# Cameralink_Karmann.net
KiCad netlist of a schematic drawn in EAGLE
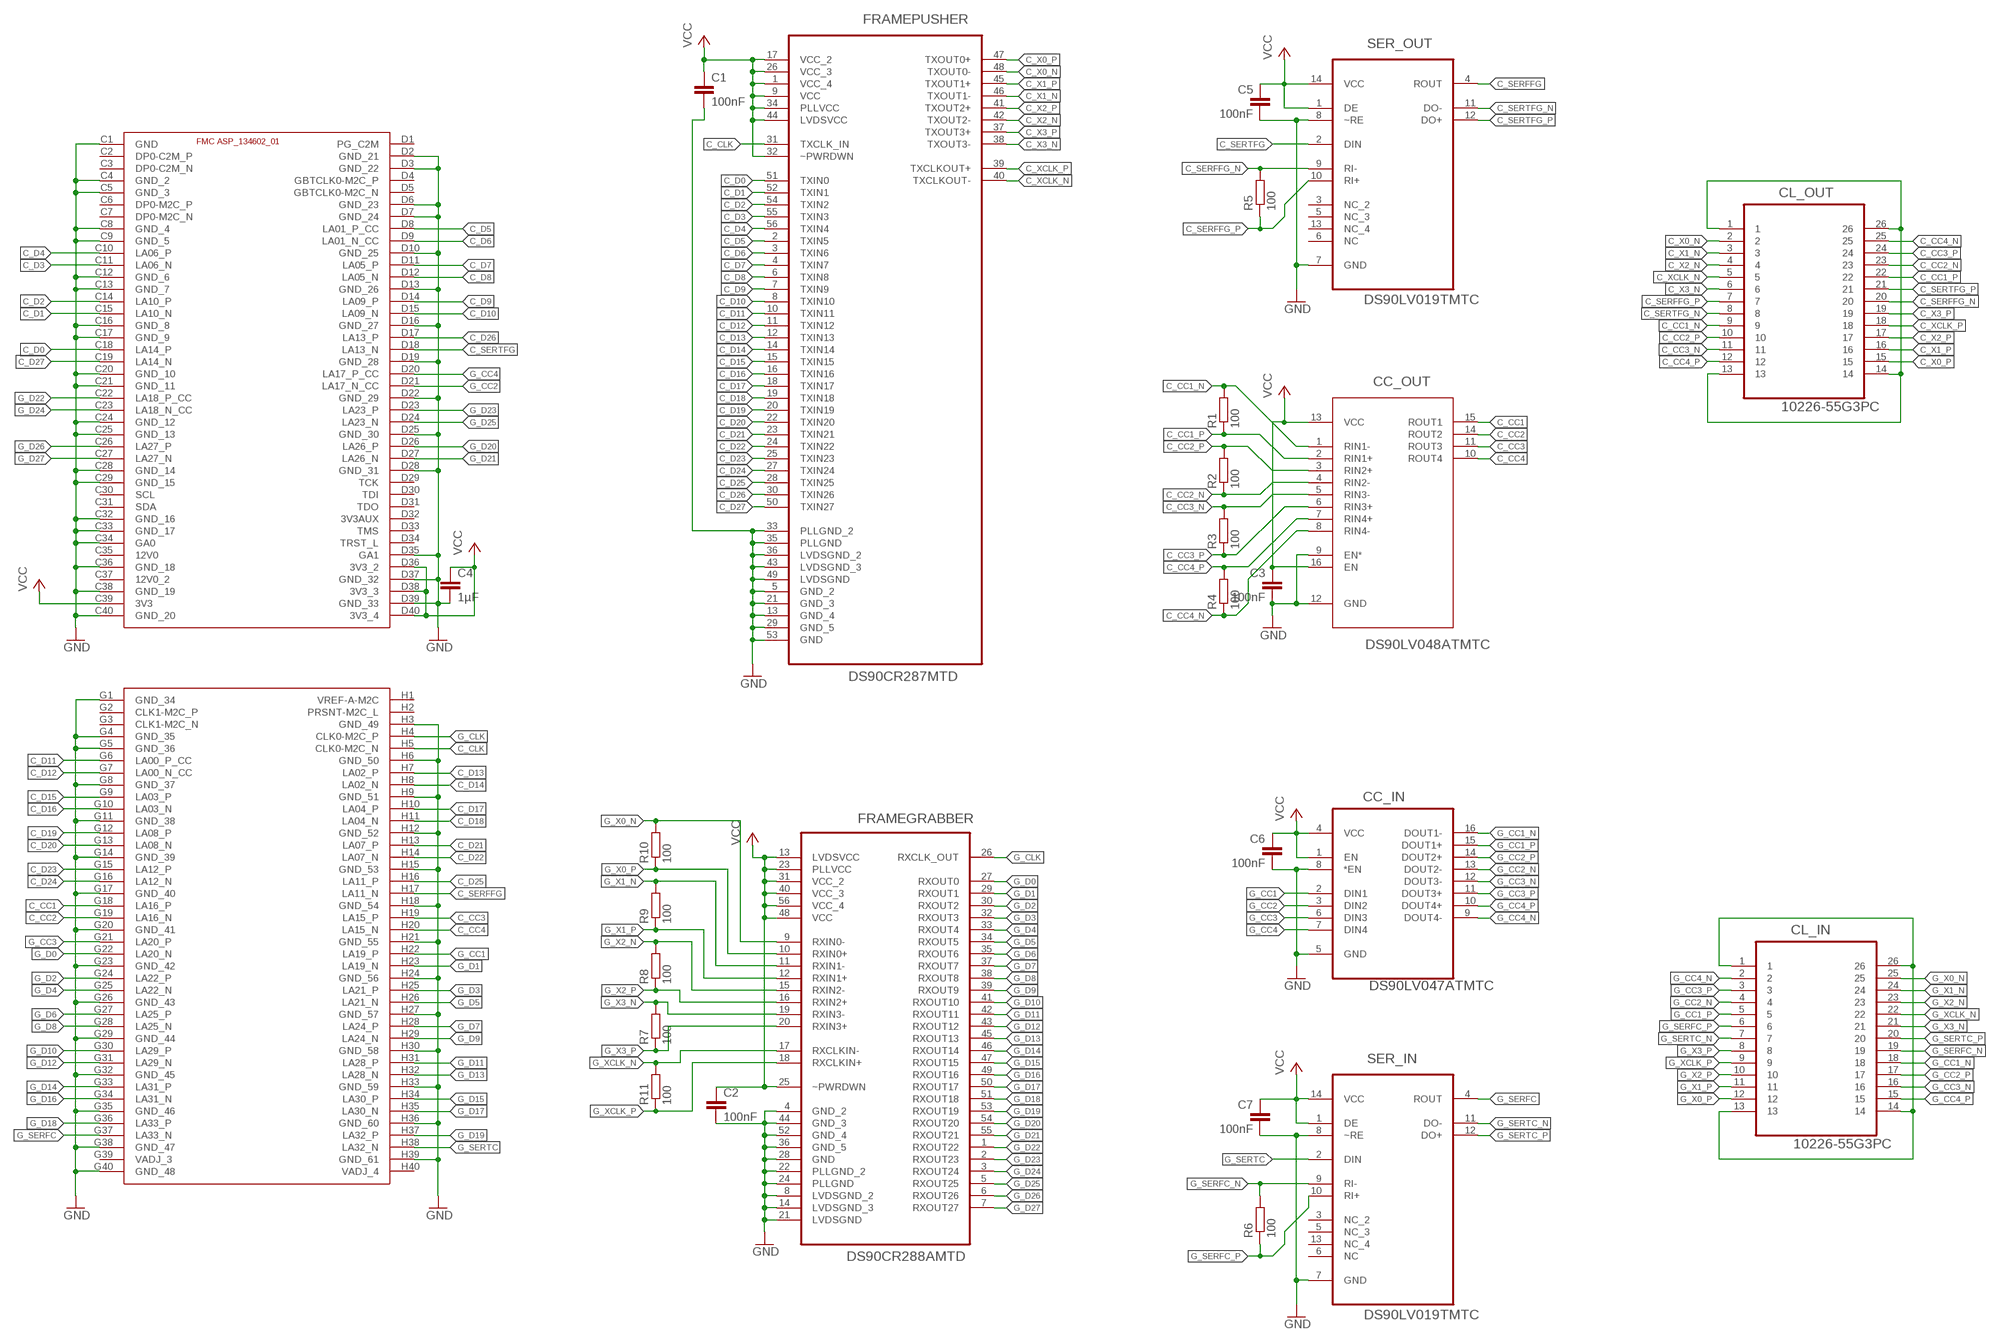
[diagram p0: schematic, sheet 1]

(export (version "E")
  (design (tool "Eeschema 10.0.6"))
  (components
    (comp (ref "C1")
      (value "100nF")
      (footprint "eagle-import:C1206")
      (libsource (lib "eagle-import") (part "C-EUC1206"))
    )
    (comp (ref "C2")
      (value "100nF")
      (footprint "eagle-import:C1206")
      (libsource (lib "eagle-import") (part "C-EUC1206"))
    )
    (comp (ref "C3")
      (value "100nF")
      (footprint "eagle-import:C1206")
      (libsource (lib "eagle-import") (part "C-EUC1206"))
    )
    (comp (ref "C4")
      (value "1µF")
      (footprint "eagle-import:C1206")
      (libsource (lib "eagle-import") (part "C-EUC1206"))
    )
    (comp (ref "C5")
      (value "100nF")
      (footprint "eagle-import:C1206")
      (libsource (lib "eagle-import") (part "C-EUC1206"))
    )
    (comp (ref "C6")
      (value "100nF")
      (footprint "eagle-import:C1206")
      (libsource (lib "eagle-import") (part "C-EUC1206"))
    )
    (comp (ref "C7")
      (value "100nF")
      (footprint "eagle-import:C1206")
      (libsource (lib "eagle-import") (part "C-EUC1206"))
    )
    (comp (ref "CC_IN")
      (value "DS90LV047ATMTC")
      (footprint "eagle-import:SOP65P640X110-16N")
      (libsource (lib "eagle-import") (part "DS90LV047ATMTC"))
    )
    (comp (ref "CC_OUT")
      (value "DS90LV048ATMTC")
      (footprint "eagle-import:SOP65P640X110-16N")
      (libsource (lib "eagle-import") (part "DS90LV048ATMTC"))
    )
    (comp (ref "CL_IN")
      (value "10226-55G3PC")
      (footprint "eagle-import:3M_10226-55G3PC")
      (libsource (lib "eagle-import") (part "10226-55G3PC"))
    )
    (comp (ref "CL_OUT")
      (value "10226-55G3PC")
      (footprint "eagle-import:3M_10226-55G3PC")
      (libsource (lib "eagle-import") (part "10226-55G3PC"))
    )
    (comp (ref "FRAMEGRABBER")
      (value "DS90CR288AMTD")
      (footprint "eagle-import:SOP50P810X110-56N")
      (libsource (lib "eagle-import") (part "DS90CR288AMTD"))
    )
    (comp (ref "FRAMEPUSHER")
      (value "DS90CR287MTD")
      (footprint "eagle-import:SOP50P810X110-56N")
      (libsource (lib "eagle-import") (part "DS90CR287MTD"))
    )
    (comp (ref "R1")
      (value "100")
      (footprint "eagle-import:R1206")
      (libsource (lib "eagle-import") (part "R-EU_R1206"))
    )
    (comp (ref "R2")
      (value "100")
      (footprint "eagle-import:R1206")
      (libsource (lib "eagle-import") (part "R-EU_R1206"))
    )
    (comp (ref "R3")
      (value "100")
      (footprint "eagle-import:R1206")
      (libsource (lib "eagle-import") (part "R-EU_R1206"))
    )
    (comp (ref "R4")
      (value "100")
      (footprint "eagle-import:R1206")
      (libsource (lib "eagle-import") (part "R-EU_R1206"))
    )
    (comp (ref "R5")
      (value "100")
      (footprint "eagle-import:R1206")
      (libsource (lib "eagle-import") (part "R-EU_R1206"))
    )
    (comp (ref "R6")
      (value "100")
      (footprint "eagle-import:R1206")
      (libsource (lib "eagle-import") (part "R-EU_R1206"))
    )
    (comp (ref "R7")
      (value "100")
      (footprint "eagle-import:R1206")
      (libsource (lib "eagle-import") (part "R-EU_R1206"))
    )
    (comp (ref "R8")
      (value "100")
      (footprint "eagle-import:R1206")
      (libsource (lib "eagle-import") (part "R-EU_R1206"))
    )
    (comp (ref "R9")
      (value "100")
      (footprint "eagle-import:R1206")
      (libsource (lib "eagle-import") (part "R-EU_R1206"))
    )
    (comp (ref "R10")
      (value "100")
      (footprint "eagle-import:R1206")
      (libsource (lib "eagle-import") (part "R-EU_R1206"))
    )
    (comp (ref "R11")
      (value "100")
      (footprint "eagle-import:R1206")
      (libsource (lib "eagle-import") (part "R-EU_R1206"))
    )
    (comp (ref "SER_IN")
      (value "DS90LV019TMTC")
      (footprint "eagle-import:SOP65P640X110-14N")
      (libsource (lib "eagle-import") (part "DS90LV019TMTC"))
    )
    (comp (ref "SER_OUT")
      (value "DS90LV019TMTC")
      (footprint "eagle-import:SOP65P640X110-14N")
      (libsource (lib "eagle-import") (part "DS90LV019TMTC"))
    )
    (comp (ref "U$1")
      (value "ASP_134602_01")
      (footprint "eagle-import:ASP_134602_01")
      (libsource (lib "eagle-import") (part "ASP_134602_01"))
    )
  )
  (nets
    (net (code "1") (name "C_CC1") (class "Default")
      (node (ref "CC_OUT") (pin "15") (pinfunction "ROUT1_15") (pintype "output"))
      (node (ref "U$1") (pin "G18") (pinfunction "LA16_P_G18") (pintype "bidirectional"))
    )
    (net (code "2") (name "C_CC1_N") (class "Default")
      (node (ref "CC_OUT") (pin "1") (pinfunction "RIN1-_1") (pintype "input"))
      (node (ref "CL_OUT") (pin "9") (pinfunction "9_9") (pintype "passive"))
      (node (ref "R1") (pin "2") (pinfunction "2_2") (pintype "passive"))
    )
    (net (code "3") (name "C_CC1_P") (class "Default")
      (node (ref "CC_OUT") (pin "2") (pinfunction "RIN1+_2") (pintype "input"))
      (node (ref "CL_OUT") (pin "22") (pinfunction "22_22") (pintype "passive"))
      (node (ref "R1") (pin "1") (pinfunction "1_1") (pintype "passive"))
    )
    (net (code "4") (name "C_CC2") (class "Default")
      (node (ref "CC_OUT") (pin "14") (pinfunction "ROUT2_14") (pintype "output"))
      (node (ref "U$1") (pin "G19") (pinfunction "LA16_N_G19") (pintype "bidirectional"))
    )
    (net (code "5") (name "C_CC2_N") (class "Default")
      (node (ref "CC_OUT") (pin "4") (pinfunction "RIN2-_4") (pintype "input"))
      (node (ref "CL_OUT") (pin "23") (pinfunction "23_23") (pintype "passive"))
      (node (ref "R2") (pin "1") (pinfunction "1_1") (pintype "passive"))
    )
    (net (code "6") (name "C_CC2_P") (class "Default")
      (node (ref "CC_OUT") (pin "3") (pinfunction "RIN2+_3") (pintype "input"))
      (node (ref "CL_OUT") (pin "10") (pinfunction "10_10") (pintype "passive"))
      (node (ref "R2") (pin "2") (pinfunction "2_2") (pintype "passive"))
    )
    (net (code "7") (name "C_CC3") (class "Default")
      (node (ref "CC_OUT") (pin "11") (pinfunction "ROUT3_11") (pintype "output"))
      (node (ref "U$1") (pin "H19") (pinfunction "LA15_P_H19") (pintype "bidirectional"))
    )
    (net (code "8") (name "C_CC3_N") (class "Default")
      (node (ref "CC_OUT") (pin "5") (pinfunction "RIN3-_5") (pintype "input"))
      (node (ref "CL_OUT") (pin "11") (pinfunction "11_11") (pintype "passive"))
      (node (ref "R3") (pin "2") (pinfunction "2_2") (pintype "passive"))
    )
    (net (code "9") (name "C_CC3_P") (class "Default")
      (node (ref "CC_OUT") (pin "6") (pinfunction "RIN3+_6") (pintype "input"))
      (node (ref "CL_OUT") (pin "24") (pinfunction "24_24") (pintype "passive"))
      (node (ref "R3") (pin "1") (pinfunction "1_1") (pintype "passive"))
    )
    (net (code "10") (name "C_CC4") (class "Default")
      (node (ref "CC_OUT") (pin "10") (pinfunction "ROUT4_10") (pintype "output"))
      (node (ref "U$1") (pin "H20") (pinfunction "LA15_N_H20") (pintype "bidirectional"))
    )
    (net (code "11") (name "C_CC4_N") (class "Default")
      (node (ref "CC_OUT") (pin "8") (pinfunction "RIN4-_8") (pintype "input"))
      (node (ref "CL_OUT") (pin "25") (pinfunction "25_25") (pintype "passive"))
      (node (ref "R4") (pin "1") (pinfunction "1_1") (pintype "passive"))
    )
    (net (code "12") (name "C_CC4_P") (class "Default")
      (node (ref "CC_OUT") (pin "7") (pinfunction "RIN4+_7") (pintype "input"))
      (node (ref "CL_OUT") (pin "12") (pinfunction "12_12") (pintype "passive"))
      (node (ref "R4") (pin "2") (pinfunction "2_2") (pintype "passive"))
    )
    (net (code "13") (name "C_CLK") (class "Default")
      (node (ref "FRAMEPUSHER") (pin "31") (pinfunction "TXCLK_IN_31") (pintype "input"))
      (node (ref "U$1") (pin "H5") (pinfunction "CLK0-M2C_N_H5") (pintype "bidirectional"))
    )
    (net (code "14") (name "C_D0") (class "Default")
      (node (ref "FRAMEPUSHER") (pin "51") (pinfunction "TXIN0_51") (pintype "input"))
      (node (ref "U$1") (pin "C18") (pinfunction "LA14_P_C18") (pintype "bidirectional"))
    )
    (net (code "15") (name "C_D1") (class "Default")
      (node (ref "FRAMEPUSHER") (pin "52") (pinfunction "TXIN1_52") (pintype "input"))
      (node (ref "U$1") (pin "C15") (pinfunction "LA10_N_C15") (pintype "bidirectional"))
    )
    (net (code "16") (name "C_D2") (class "Default")
      (node (ref "FRAMEPUSHER") (pin "54") (pinfunction "TXIN2_54") (pintype "input"))
      (node (ref "U$1") (pin "C14") (pinfunction "LA10_P_C14") (pintype "bidirectional"))
    )
    (net (code "17") (name "C_D3") (class "Default")
      (node (ref "FRAMEPUSHER") (pin "55") (pinfunction "TXIN3_55") (pintype "input"))
      (node (ref "U$1") (pin "C11") (pinfunction "LA06_N_C11") (pintype "bidirectional"))
    )
    (net (code "18") (name "C_D4") (class "Default")
      (node (ref "FRAMEPUSHER") (pin "56") (pinfunction "TXIN4_56") (pintype "input"))
      (node (ref "U$1") (pin "C10") (pinfunction "LA06_P_C10") (pintype "bidirectional"))
    )
    (net (code "19") (name "C_D5") (class "Default")
      (node (ref "FRAMEPUSHER") (pin "2") (pinfunction "TXIN5_2") (pintype "input"))
      (node (ref "U$1") (pin "D8") (pinfunction "LA01_P_CC_D8") (pintype "bidirectional"))
    )
    (net (code "20") (name "C_D6") (class "Default")
      (node (ref "FRAMEPUSHER") (pin "3") (pinfunction "TXIN6_3") (pintype "input"))
      (node (ref "U$1") (pin "D9") (pinfunction "LA01_N_CC_D9") (pintype "bidirectional"))
    )
    (net (code "21") (name "C_D7") (class "Default")
      (node (ref "FRAMEPUSHER") (pin "4") (pinfunction "TXIN7_4") (pintype "input"))
      (node (ref "U$1") (pin "D11") (pinfunction "LA05_P_D11") (pintype "bidirectional"))
    )
    (net (code "22") (name "C_D8") (class "Default")
      (node (ref "FRAMEPUSHER") (pin "6") (pinfunction "TXIN8_6") (pintype "input"))
      (node (ref "U$1") (pin "D12") (pinfunction "LA05_N_D12") (pintype "bidirectional"))
    )
    (net (code "23") (name "C_D9") (class "Default")
      (node (ref "FRAMEPUSHER") (pin "7") (pinfunction "TXIN9_7") (pintype "input"))
      (node (ref "U$1") (pin "D14") (pinfunction "LA09_P_D14") (pintype "bidirectional"))
    )
    (net (code "24") (name "C_D10") (class "Default")
      (node (ref "FRAMEPUSHER") (pin "8") (pinfunction "TXIN10_8") (pintype "input"))
      (node (ref "U$1") (pin "D15") (pinfunction "LA09_N_D15") (pintype "bidirectional"))
    )
    (net (code "25") (name "C_D11") (class "Default")
      (node (ref "FRAMEPUSHER") (pin "10") (pinfunction "TXIN11_10") (pintype "input"))
      (node (ref "U$1") (pin "G6") (pinfunction "LA00_P_CC_G6") (pintype "bidirectional"))
    )
    (net (code "26") (name "C_D12") (class "Default")
      (node (ref "FRAMEPUSHER") (pin "11") (pinfunction "TXIN12_11") (pintype "input"))
      (node (ref "U$1") (pin "G7") (pinfunction "LA00_N_CC_G7") (pintype "bidirectional"))
    )
    (net (code "27") (name "C_D13") (class "Default")
      (node (ref "FRAMEPUSHER") (pin "12") (pinfunction "TXIN13_12") (pintype "input"))
      (node (ref "U$1") (pin "H7") (pinfunction "LA02_P_H7") (pintype "bidirectional"))
    )
    (net (code "28") (name "C_D14") (class "Default")
      (node (ref "FRAMEPUSHER") (pin "14") (pinfunction "TXIN14_14") (pintype "input"))
      (node (ref "U$1") (pin "H8") (pinfunction "LA02_N_H8") (pintype "bidirectional"))
    )
    (net (code "29") (name "C_D15") (class "Default")
      (node (ref "FRAMEPUSHER") (pin "15") (pinfunction "TXIN15_15") (pintype "input"))
      (node (ref "U$1") (pin "G9") (pinfunction "LA03_P_G9") (pintype "bidirectional"))
    )
    (net (code "30") (name "C_D16") (class "Default")
      (node (ref "FRAMEPUSHER") (pin "16") (pinfunction "TXIN16_16") (pintype "input"))
      (node (ref "U$1") (pin "G10") (pinfunction "LA03_N_G10") (pintype "bidirectional"))
    )
    (net (code "31") (name "C_D17") (class "Default")
      (node (ref "FRAMEPUSHER") (pin "18") (pinfunction "TXIN17_18") (pintype "input"))
      (node (ref "U$1") (pin "H10") (pinfunction "LA04_P_H10") (pintype "bidirectional"))
    )
    (net (code "32") (name "C_D18") (class "Default")
      (node (ref "FRAMEPUSHER") (pin "19") (pinfunction "TXIN18_19") (pintype "input"))
      (node (ref "U$1") (pin "H11") (pinfunction "LA04_N_H11") (pintype "bidirectional"))
    )
    (net (code "33") (name "C_D19") (class "Default")
      (node (ref "FRAMEPUSHER") (pin "20") (pinfunction "TXIN19_20") (pintype "input"))
      (node (ref "U$1") (pin "G12") (pinfunction "LA08_P_G12") (pintype "bidirectional"))
    )
    (net (code "34") (name "C_D20") (class "Default")
      (node (ref "FRAMEPUSHER") (pin "22") (pinfunction "TXIN20_22") (pintype "input"))
      (node (ref "U$1") (pin "G13") (pinfunction "LA08_N_G13") (pintype "bidirectional"))
    )
    (net (code "35") (name "C_D21") (class "Default")
      (node (ref "FRAMEPUSHER") (pin "23") (pinfunction "TXIN21_23") (pintype "input"))
      (node (ref "U$1") (pin "H13") (pinfunction "LA07_P_H13") (pintype "bidirectional"))
    )
    (net (code "36") (name "C_D22") (class "Default")
      (node (ref "FRAMEPUSHER") (pin "24") (pinfunction "TXIN22_24") (pintype "input"))
      (node (ref "U$1") (pin "H14") (pinfunction "LA07_N_H14") (pintype "bidirectional"))
    )
    (net (code "37") (name "C_D23") (class "Default")
      (node (ref "FRAMEPUSHER") (pin "25") (pinfunction "TXIN23_25") (pintype "input"))
      (node (ref "U$1") (pin "G15") (pinfunction "LA12_P_G15") (pintype "bidirectional"))
    )
    (net (code "38") (name "C_D24") (class "Default")
      (node (ref "FRAMEPUSHER") (pin "27") (pinfunction "TXIN24_27") (pintype "input"))
      (node (ref "U$1") (pin "G16") (pinfunction "LA12_N_G16") (pintype "bidirectional"))
    )
    (net (code "39") (name "C_D25") (class "Default")
      (node (ref "FRAMEPUSHER") (pin "28") (pinfunction "TXIN25_28") (pintype "input"))
      (node (ref "U$1") (pin "H16") (pinfunction "LA11_P_H16") (pintype "bidirectional"))
    )
    (net (code "40") (name "C_D26") (class "Default")
      (node (ref "FRAMEPUSHER") (pin "30") (pinfunction "TXIN26_30") (pintype "input"))
      (node (ref "U$1") (pin "D17") (pinfunction "LA13_P_D17") (pintype "bidirectional"))
    )
    (net (code "41") (name "C_D27") (class "Default")
      (node (ref "FRAMEPUSHER") (pin "50") (pinfunction "TXIN27_50") (pintype "input"))
      (node (ref "U$1") (pin "C19") (pinfunction "LA14_N_C19") (pintype "bidirectional"))
    )
    (net (code "42") (name "C_SERFFG") (class "Default")
      (node (ref "SER_OUT") (pin "4") (pinfunction "ROUT_4") (pintype "output"))
      (node (ref "U$1") (pin "H17") (pinfunction "LA11_N_H17") (pintype "bidirectional"))
    )
    (net (code "43") (name "C_SERFFG_N") (class "Default")
      (node (ref "CL_OUT") (pin "20") (pinfunction "20_20") (pintype "passive"))
      (node (ref "R5") (pin "2") (pinfunction "2_2") (pintype "passive"))
      (node (ref "SER_OUT") (pin "9") (pinfunction "RI-_9") (pintype "input"))
    )
    (net (code "44") (name "C_SERFFG_P") (class "Default")
      (node (ref "CL_OUT") (pin "7") (pinfunction "7_7") (pintype "passive"))
      (node (ref "R5") (pin "1") (pinfunction "1_1") (pintype "passive"))
      (node (ref "SER_OUT") (pin "10") (pinfunction "RI+_10") (pintype "input"))
    )
    (net (code "45") (name "C_SERTFG") (class "Default")
      (node (ref "SER_OUT") (pin "2") (pinfunction "DIN_2") (pintype "input"))
      (node (ref "U$1") (pin "D18") (pinfunction "LA13_N_D18") (pintype "bidirectional"))
    )
    (net (code "46") (name "C_SERTFG_N") (class "Default")
      (node (ref "CL_OUT") (pin "8") (pinfunction "8_8") (pintype "passive"))
      (node (ref "SER_OUT") (pin "11") (pinfunction "DO-_11") (pintype "output"))
    )
    (net (code "47") (name "C_SERTFG_P") (class "Default")
      (node (ref "CL_OUT") (pin "21") (pinfunction "21_21") (pintype "passive"))
      (node (ref "SER_OUT") (pin "12") (pinfunction "DO+_12") (pintype "output"))
    )
    (net (code "48") (name "C_X0_N") (class "Default")
      (node (ref "CL_OUT") (pin "2") (pinfunction "2_2") (pintype "passive"))
      (node (ref "FRAMEPUSHER") (pin "48") (pinfunction "TXOUT0-_48") (pintype "output"))
    )
    (net (code "49") (name "C_X0_P") (class "Default")
      (node (ref "CL_OUT") (pin "15") (pinfunction "15_15") (pintype "passive"))
      (node (ref "FRAMEPUSHER") (pin "47") (pinfunction "TXOUT0+_47") (pintype "output"))
    )
    (net (code "50") (name "C_X1_N") (class "Default")
      (node (ref "CL_OUT") (pin "3") (pinfunction "3_3") (pintype "passive"))
      (node (ref "FRAMEPUSHER") (pin "46") (pinfunction "TXOUT1-_46") (pintype "output"))
    )
    (net (code "51") (name "C_X1_P") (class "Default")
      (node (ref "CL_OUT") (pin "16") (pinfunction "16_16") (pintype "passive"))
      (node (ref "FRAMEPUSHER") (pin "45") (pinfunction "TXOUT1+_45") (pintype "output"))
    )
    (net (code "52") (name "C_X2_N") (class "Default")
      (node (ref "CL_OUT") (pin "4") (pinfunction "4_4") (pintype "passive"))
      (node (ref "FRAMEPUSHER") (pin "42") (pinfunction "TXOUT2-_42") (pintype "output"))
    )
    (net (code "53") (name "C_X2_P") (class "Default")
      (node (ref "CL_OUT") (pin "17") (pinfunction "17_17") (pintype "passive"))
      (node (ref "FRAMEPUSHER") (pin "41") (pinfunction "TXOUT2+_41") (pintype "output"))
    )
    (net (code "54") (name "C_X3_N") (class "Default")
      (node (ref "CL_OUT") (pin "6") (pinfunction "6_6") (pintype "passive"))
      (node (ref "FRAMEPUSHER") (pin "38") (pinfunction "TXOUT3-_38") (pintype "output"))
    )
    (net (code "55") (name "C_X3_P") (class "Default")
      (node (ref "CL_OUT") (pin "19") (pinfunction "19_19") (pintype "passive"))
      (node (ref "FRAMEPUSHER") (pin "37") (pinfunction "TXOUT3+_37") (pintype "output"))
    )
    (net (code "56") (name "C_XCLK_N") (class "Default")
      (node (ref "CL_OUT") (pin "5") (pinfunction "5_5") (pintype "passive"))
      (node (ref "FRAMEPUSHER") (pin "40") (pinfunction "TXCLKOUT-_40") (pintype "output"))
    )
    (net (code "57") (name "C_XCLK_P") (class "Default")
      (node (ref "CL_OUT") (pin "18") (pinfunction "18_18") (pintype "passive"))
      (node (ref "FRAMEPUSHER") (pin "39") (pinfunction "TXCLKOUT+_39") (pintype "output"))
    )
    (net (code "58") (name "GND") (class "Default")
      (node (ref "C1") (pin "2") (pinfunction "2_2") (pintype "passive"))
      (node (ref "C2") (pin "2") (pinfunction "2_2") (pintype "passive"))
      (node (ref "C3") (pin "2") (pinfunction "2_2") (pintype "passive"))
      (node (ref "C4") (pin "2") (pinfunction "2_2") (pintype "passive"))
      (node (ref "C5") (pin "2") (pinfunction "2_2") (pintype "passive"))
      (node (ref "C6") (pin "2") (pinfunction "2_2") (pintype "passive"))
      (node (ref "C7") (pin "2") (pinfunction "2_2") (pintype "passive"))
      (node (ref "CC_IN") (pin "5") (pinfunction "GND_5") (pintype "passive"))
      (node (ref "CC_IN") (pin "8") (pinfunction "*EN_8") (pintype "input"))
      (node (ref "CC_OUT") (pin "12") (pinfunction "GND_12") (pintype "passive"))
      (node (ref "CC_OUT") (pin "9") (pinfunction "EN*_9") (pintype "input"))
      (node (ref "FRAMEGRABBER") (pin "14") (pinfunction "LVDSGND_3_14") (pintype "passive"))
      (node (ref "FRAMEGRABBER") (pin "21") (pinfunction "LVDSGND_21") (pintype "passive"))
      (node (ref "FRAMEGRABBER") (pin "22") (pinfunction "PLLGND_2_22") (pintype "passive"))
      (node (ref "FRAMEGRABBER") (pin "24") (pinfunction "PLLGND_24") (pintype "power_in"))
      (node (ref "FRAMEGRABBER") (pin "28") (pinfunction "GND_28") (pintype "passive"))
      (node (ref "FRAMEGRABBER") (pin "36") (pinfunction "GND_5_36") (pintype "passive"))
      (node (ref "FRAMEGRABBER") (pin "4") (pinfunction "GND_2_4") (pintype "passive"))
      (node (ref "FRAMEGRABBER") (pin "44") (pinfunction "GND_3_44") (pintype "passive"))
      (node (ref "FRAMEGRABBER") (pin "52") (pinfunction "GND_4_52") (pintype "passive"))
      (node (ref "FRAMEGRABBER") (pin "8") (pinfunction "LVDSGND_2_8") (pintype "passive"))
      (node (ref "FRAMEPUSHER") (pin "13") (pinfunction "GND_4_13") (pintype "passive"))
      (node (ref "FRAMEPUSHER") (pin "21") (pinfunction "GND_3_21") (pintype "passive"))
      (node (ref "FRAMEPUSHER") (pin "29") (pinfunction "GND_5_29") (pintype "passive"))
      (node (ref "FRAMEPUSHER") (pin "33") (pinfunction "PLLGND_2_33") (pintype "passive"))
      (node (ref "FRAMEPUSHER") (pin "35") (pinfunction "PLLGND_35") (pintype "passive"))
      (node (ref "FRAMEPUSHER") (pin "36") (pinfunction "LVDSGND_2_36") (pintype "passive"))
      (node (ref "FRAMEPUSHER") (pin "43") (pinfunction "LVDSGND_3_43") (pintype "passive"))
      (node (ref "FRAMEPUSHER") (pin "49") (pinfunction "LVDSGND_49") (pintype "passive"))
      (node (ref "FRAMEPUSHER") (pin "5") (pinfunction "GND_2_5") (pintype "passive"))
      (node (ref "FRAMEPUSHER") (pin "53") (pinfunction "GND_53") (pintype "passive"))
      (node (ref "SER_IN") (pin "7") (pinfunction "GND_7") (pintype "passive"))
      (node (ref "SER_IN") (pin "8") (pinfunction "~{RE}_8") (pintype "input"))
      (node (ref "SER_OUT") (pin "7") (pinfunction "GND_7") (pintype "passive"))
      (node (ref "SER_OUT") (pin "8") (pinfunction "~{RE}_8") (pintype "input"))
      (node (ref "U$1") (pin "C1") (pinfunction "GND_C1") (pintype "bidirectional"))
      (node (ref "U$1") (pin "C12") (pinfunction "GND_6_C12") (pintype "bidirectional"))
      (node (ref "U$1") (pin "C13") (pinfunction "GND_7_C13") (pintype "bidirectional"))
      (node (ref "U$1") (pin "C16") (pinfunction "GND_8_C16") (pintype "bidirectional"))
      (node (ref "U$1") (pin "C17") (pinfunction "GND_9_C17") (pintype "bidirectional"))
      (node (ref "U$1") (pin "C20") (pinfunction "GND_10_C20") (pintype "bidirectional"))
      (node (ref "U$1") (pin "C21") (pinfunction "GND_11_C21") (pintype "bidirectional"))
      (node (ref "U$1") (pin "C24") (pinfunction "GND_12_C24") (pintype "bidirectional"))
      (node (ref "U$1") (pin "C25") (pinfunction "GND_13_C25") (pintype "bidirectional"))
      (node (ref "U$1") (pin "C28") (pinfunction "GND_14_C28") (pintype "bidirectional"))
      (node (ref "U$1") (pin "C29") (pinfunction "GND_15_C29") (pintype "bidirectional"))
      (node (ref "U$1") (pin "C32") (pinfunction "GND_16_C32") (pintype "bidirectional"))
      (node (ref "U$1") (pin "C33") (pinfunction "GND_17_C33") (pintype "bidirectional"))
      (node (ref "U$1") (pin "C34") (pinfunction "GA0_C34") (pintype "bidirectional"))
      (node (ref "U$1") (pin "C36") (pinfunction "GND_18_C36") (pintype "bidirectional"))
      (node (ref "U$1") (pin "C38") (pinfunction "GND_19_C38") (pintype "bidirectional"))
      (node (ref "U$1") (pin "C4") (pinfunction "GND_2_C4") (pintype "bidirectional"))
      (node (ref "U$1") (pin "C40") (pinfunction "GND_20_C40") (pintype "bidirectional"))
      (node (ref "U$1") (pin "C5") (pinfunction "GND_3_C5") (pintype "bidirectional"))
      (node (ref "U$1") (pin "C8") (pinfunction "GND_4_C8") (pintype "bidirectional"))
      (node (ref "U$1") (pin "C9") (pinfunction "GND_5_C9") (pintype "bidirectional"))
      (node (ref "U$1") (pin "D10") (pinfunction "GND_25_D10") (pintype "bidirectional"))
      (node (ref "U$1") (pin "D13") (pinfunction "GND_26_D13") (pintype "bidirectional"))
      (node (ref "U$1") (pin "D16") (pinfunction "GND_27_D16") (pintype "bidirectional"))
      (node (ref "U$1") (pin "D19") (pinfunction "GND_28_D19") (pintype "bidirectional"))
      (node (ref "U$1") (pin "D2") (pinfunction "GND_21_D2") (pintype "bidirectional"))
      (node (ref "U$1") (pin "D22") (pinfunction "GND_29_D22") (pintype "bidirectional"))
      (node (ref "U$1") (pin "D25") (pinfunction "GND_30_D25") (pintype "bidirectional"))
      (node (ref "U$1") (pin "D28") (pinfunction "GND_31_D28") (pintype "bidirectional"))
      (node (ref "U$1") (pin "D3") (pinfunction "GND_22_D3") (pintype "bidirectional"))
      (node (ref "U$1") (pin "D35") (pinfunction "GA1_D35") (pintype "bidirectional"))
      (node (ref "U$1") (pin "D37") (pinfunction "GND_32_D37") (pintype "bidirectional"))
      (node (ref "U$1") (pin "D39") (pinfunction "GND_33_D39") (pintype "bidirectional"))
      (node (ref "U$1") (pin "D6") (pinfunction "GND_23_D6") (pintype "bidirectional"))
      (node (ref "U$1") (pin "D7") (pinfunction "GND_24_D7") (pintype "bidirectional"))
      (node (ref "U$1") (pin "G1") (pinfunction "GND_34_G1") (pintype "bidirectional"))
      (node (ref "U$1") (pin "G11") (pinfunction "GND_38_G11") (pintype "bidirectional"))
      (node (ref "U$1") (pin "G14") (pinfunction "GND_39_G14") (pintype "bidirectional"))
      (node (ref "U$1") (pin "G17") (pinfunction "GND_40_G17") (pintype "bidirectional"))
      (node (ref "U$1") (pin "G20") (pinfunction "GND_41_G20") (pintype "bidirectional"))
      (node (ref "U$1") (pin "G23") (pinfunction "GND_42_G23") (pintype "bidirectional"))
      (node (ref "U$1") (pin "G26") (pinfunction "GND_43_G26") (pintype "bidirectional"))
      (node (ref "U$1") (pin "G29") (pinfunction "GND_44_G29") (pintype "bidirectional"))
      (node (ref "U$1") (pin "G32") (pinfunction "GND_45_G32") (pintype "bidirectional"))
      (node (ref "U$1") (pin "G35") (pinfunction "GND_46_G35") (pintype "bidirectional"))
      (node (ref "U$1") (pin "G38") (pinfunction "GND_47_G38") (pintype "bidirectional"))
      (node (ref "U$1") (pin "G4") (pinfunction "GND_35_G4") (pintype "bidirectional"))
      (node (ref "U$1") (pin "G40") (pinfunction "GND_48_G40") (pintype "bidirectional"))
      (node (ref "U$1") (pin "G5") (pinfunction "GND_36_G5") (pintype "bidirectional"))
      (node (ref "U$1") (pin "G8") (pinfunction "GND_37_G8") (pintype "bidirectional"))
      (node (ref "U$1") (pin "H12") (pinfunction "GND_52_H12") (pintype "bidirectional"))
      (node (ref "U$1") (pin "H15") (pinfunction "GND_53_H15") (pintype "bidirectional"))
      (node (ref "U$1") (pin "H18") (pinfunction "GND_54_H18") (pintype "bidirectional"))
      (node (ref "U$1") (pin "H21") (pinfunction "GND_55_H21") (pintype "bidirectional"))
      (node (ref "U$1") (pin "H24") (pinfunction "GND_56_H24") (pintype "bidirectional"))
      (node (ref "U$1") (pin "H27") (pinfunction "GND_57_H27") (pintype "bidirectional"))
      (node (ref "U$1") (pin "H3") (pinfunction "GND_49_H3") (pintype "bidirectional"))
      (node (ref "U$1") (pin "H30") (pinfunction "GND_58_H30") (pintype "bidirectional"))
      (node (ref "U$1") (pin "H33") (pinfunction "GND_59_H33") (pintype "bidirectional"))
      (node (ref "U$1") (pin "H36") (pinfunction "GND_60_H36") (pintype "bidirectional"))
      (node (ref "U$1") (pin "H39") (pinfunction "GND_61_H39") (pintype "bidirectional"))
      (node (ref "U$1") (pin "H6") (pinfunction "GND_50_H6") (pintype "bidirectional"))
      (node (ref "U$1") (pin "H9") (pinfunction "GND_51_H9") (pintype "bidirectional"))
    )
    (net (code "59") (name "G_CC1") (class "Default")
      (node (ref "CC_IN") (pin "2") (pinfunction "DIN1_2") (pintype "input"))
      (node (ref "U$1") (pin "H22") (pinfunction "LA19_P_H22") (pintype "bidirectional"))
    )
    (net (code "60") (name "G_CC1_N") (class "Default")
      (node (ref "CC_IN") (pin "16") (pinfunction "DOUT1-_16") (pintype "output"))
      (node (ref "CL_IN") (pin "18") (pinfunction "18_18") (pintype "passive"))
    )
    (net (code "61") (name "G_CC1_P") (class "Default")
      (node (ref "CC_IN") (pin "15") (pinfunction "DOUT1+_15") (pintype "output"))
      (node (ref "CL_IN") (pin "5") (pinfunction "5_5") (pintype "passive"))
    )
    (net (code "62") (name "G_CC2") (class "Default")
      (node (ref "CC_IN") (pin "3") (pinfunction "DIN2_3") (pintype "input"))
      (node (ref "U$1") (pin "D21") (pinfunction "LA17_N_CC_D21") (pintype "bidirectional"))
    )
    (net (code "63") (name "G_CC2_N") (class "Default")
      (node (ref "CC_IN") (pin "13") (pinfunction "DOUT2-_13") (pintype "output"))
      (node (ref "CL_IN") (pin "4") (pinfunction "4_4") (pintype "passive"))
    )
    (net (code "64") (name "G_CC2_P") (class "Default")
      (node (ref "CC_IN") (pin "14") (pinfunction "DOUT2+_14") (pintype "output"))
      (node (ref "CL_IN") (pin "17") (pinfunction "17_17") (pintype "passive"))
    )
    (net (code "65") (name "G_CC3") (class "Default")
      (node (ref "CC_IN") (pin "6") (pinfunction "DIN3_6") (pintype "input"))
      (node (ref "U$1") (pin "G21") (pinfunction "LA20_P_G21") (pintype "bidirectional"))
    )
    (net (code "66") (name "G_CC3_N") (class "Default")
      (node (ref "CC_IN") (pin "12") (pinfunction "DOUT3-_12") (pintype "output"))
      (node (ref "CL_IN") (pin "16") (pinfunction "16_16") (pintype "passive"))
    )
    (net (code "67") (name "G_CC3_P") (class "Default")
      (node (ref "CC_IN") (pin "11") (pinfunction "DOUT3+_11") (pintype "output"))
      (node (ref "CL_IN") (pin "3") (pinfunction "3_3") (pintype "passive"))
    )
    (net (code "68") (name "G_CC4") (class "Default")
      (node (ref "CC_IN") (pin "7") (pinfunction "DIN4_7") (pintype "input"))
      (node (ref "U$1") (pin "D20") (pinfunction "LA17_P_CC_D20") (pintype "bidirectional"))
    )
    (net (code "69") (name "G_CC4_N") (class "Default")
      (node (ref "CC_IN") (pin "9") (pinfunction "DOUT4-_9") (pintype "output"))
      (node (ref "CL_IN") (pin "2") (pinfunction "2_2") (pintype "passive"))
    )
    (net (code "70") (name "G_CC4_P") (class "Default")
      (node (ref "CC_IN") (pin "10") (pinfunction "DOUT4+_10") (pintype "output"))
      (node (ref "CL_IN") (pin "15") (pinfunction "15_15") (pintype "passive"))
    )
    (net (code "71") (name "G_CLK") (class "Default")
      (node (ref "FRAMEGRABBER") (pin "26") (pinfunction "RXCLK_OUT_26") (pintype "output"))
      (node (ref "U$1") (pin "H4") (pinfunction "CLK0-M2C_P_H4") (pintype "bidirectional"))
    )
    (net (code "72") (name "G_D0") (class "Default")
      (node (ref "FRAMEGRABBER") (pin "27") (pinfunction "RXOUT0_27") (pintype "output"))
      (node (ref "U$1") (pin "G22") (pinfunction "LA20_N_G22") (pintype "bidirectional"))
    )
    (net (code "73") (name "G_D1") (class "Default")
      (node (ref "FRAMEGRABBER") (pin "29") (pinfunction "RXOUT1_29") (pintype "output"))
      (node (ref "U$1") (pin "H23") (pinfunction "LA19_N_H23") (pintype "bidirectional"))
    )
    (net (code "74") (name "G_D2") (class "Default")
      (node (ref "FRAMEGRABBER") (pin "30") (pinfunction "RXOUT2_30") (pintype "output"))
      (node (ref "U$1") (pin "G24") (pinfunction "LA22_P_G24") (pintype "bidirectional"))
    )
    (net (code "75") (name "G_D3") (class "Default")
      (node (ref "FRAMEGRABBER") (pin "32") (pinfunction "RXOUT3_32") (pintype "output"))
      (node (ref "U$1") (pin "H25") (pinfunction "LA21_P_H25") (pintype "bidirectional"))
    )
    (net (code "76") (name "G_D4") (class "Default")
      (node (ref "FRAMEGRABBER") (pin "33") (pinfunction "RXOUT4_33") (pintype "output"))
      (node (ref "U$1") (pin "G25") (pinfunction "LA22_N_G25") (pintype "bidirectional"))
    )
    (net (code "77") (name "G_D5") (class "Default")
      (node (ref "FRAMEGRABBER") (pin "34") (pinfunction "RXOUT5_34") (pintype "output"))
      (node (ref "U$1") (pin "H26") (pinfunction "LA21_N_H26") (pintype "bidirectional"))
    )
    (net (code "78") (name "G_D6") (class "Default")
      (node (ref "FRAMEGRABBER") (pin "35") (pinfunction "RXOUT6_35") (pintype "output"))
      (node (ref "U$1") (pin "G27") (pinfunction "LA25_P_G27") (pintype "bidirectional"))
    )
    (net (code "79") (name "G_D7") (class "Default")
      (node (ref "FRAMEGRABBER") (pin "37") (pinfunction "RXOUT7_37") (pintype "output"))
      (node (ref "U$1") (pin "H28") (pinfunction "LA24_P_H28") (pintype "bidirectional"))
    )
    (net (code "80") (name "G_D8") (class "Default")
      (node (ref "FRAMEGRABBER") (pin "38") (pinfunction "RXOUT8_38") (pintype "output"))
      (node (ref "U$1") (pin "G28") (pinfunction "LA25_N_G28") (pintype "bidirectional"))
    )
    (net (code "81") (name "G_D9") (class "Default")
      (node (ref "FRAMEGRABBER") (pin "39") (pinfunction "RXOUT9_39") (pintype "output"))
      (node (ref "U$1") (pin "H29") (pinfunction "LA24_N_H29") (pintype "bidirectional"))
    )
    (net (code "82") (name "G_D10") (class "Default")
      (node (ref "FRAMEGRABBER") (pin "41") (pinfunction "RXOUT10_41") (pintype "output"))
      (node (ref "U$1") (pin "G30") (pinfunction "LA29_P_G30") (pintype "bidirectional"))
    )
    (net (code "83") (name "G_D11") (class "Default")
      (node (ref "FRAMEGRABBER") (pin "42") (pinfunction "RXOUT11_42") (pintype "output"))
      (node (ref "U$1") (pin "H31") (pinfunction "LA28_P_H31") (pintype "bidirectional"))
    )
    (net (code "84") (name "G_D12") (class "Default")
      (node (ref "FRAMEGRABBER") (pin "43") (pinfunction "RXOUT12_43") (pintype "output"))
      (node (ref "U$1") (pin "G31") (pinfunction "LA29_N_G31") (pintype "bidirectional"))
    )
    (net (code "85") (name "G_D13") (class "Default")
      (node (ref "FRAMEGRABBER") (pin "45") (pinfunction "RXOUT13_45") (pintype "output"))
      (node (ref "U$1") (pin "H32") (pinfunction "LA28_N_H32") (pintype "bidirectional"))
    )
    (net (code "86") (name "G_D14") (class "Default")
      (node (ref "FRAMEGRABBER") (pin "46") (pinfunction "RXOUT14_46") (pintype "output"))
      (node (ref "U$1") (pin "G33") (pinfunction "LA31_P_G33") (pintype "bidirectional"))
    )
    (net (code "87") (name "G_D15") (class "Default")
      (node (ref "FRAMEGRABBER") (pin "47") (pinfunction "RXOUT15_47") (pintype "output"))
      (node (ref "U$1") (pin "H34") (pinfunction "LA30_P_H34") (pintype "bidirectional"))
    )
    (net (code "88") (name "G_D16") (class "Default")
      (node (ref "FRAMEGRABBER") (pin "49") (pinfunction "RXOUT16_49") (pintype "output"))
      (node (ref "U$1") (pin "G34") (pinfunction "LA31_N_G34") (pintype "bidirectional"))
    )
    (net (code "89") (name "G_D17") (class "Default")
      (node (ref "FRAMEGRABBER") (pin "50") (pinfunction "RXOUT17_50") (pintype "output"))
      (node (ref "U$1") (pin "H35") (pinfunction "LA30_N_H35") (pintype "bidirectional"))
    )
    (net (code "90") (name "G_D18") (class "Default")
      (node (ref "FRAMEGRABBER") (pin "51") (pinfunction "RXOUT18_51") (pintype "output"))
      (node (ref "U$1") (pin "G36") (pinfunction "LA33_P_G36") (pintype "bidirectional"))
    )
    (net (code "91") (name "G_D19") (class "Default")
      (node (ref "FRAMEGRABBER") (pin "53") (pinfunction "RXOUT19_53") (pintype "output"))
      (node (ref "U$1") (pin "H37") (pinfunction "LA32_P_H37") (pintype "bidirectional"))
    )
    (net (code "92") (name "G_D20") (class "Default")
      (node (ref "FRAMEGRABBER") (pin "54") (pinfunction "RXOUT20_54") (pintype "output"))
      (node (ref "U$1") (pin "D26") (pinfunction "LA26_P_D26") (pintype "bidirectional"))
    )
    (net (code "93") (name "G_D21") (class "Default")
      (node (ref "FRAMEGRABBER") (pin "55") (pinfunction "RXOUT21_55") (pintype "output"))
      (node (ref "U$1") (pin "D27") (pinfunction "LA26_N_D27") (pintype "bidirectional"))
    )
    (net (code "94") (name "G_D22") (class "Default")
      (node (ref "FRAMEGRABBER") (pin "1") (pinfunction "RXOUT22_1") (pintype "output"))
      (node (ref "U$1") (pin "C22") (pinfunction "LA18_P_CC_C22") (pintype "bidirectional"))
    )
    (net (code "95") (name "G_D23") (class "Default")
      (node (ref "FRAMEGRABBER") (pin "2") (pinfunction "RXOUT23_2") (pintype "output"))
      (node (ref "U$1") (pin "D23") (pinfunction "LA23_P_D23") (pintype "bidirectional"))
    )
    (net (code "96") (name "G_D24") (class "Default")
      (node (ref "FRAMEGRABBER") (pin "3") (pinfunction "RXOUT24_3") (pintype "output"))
      (node (ref "U$1") (pin "C23") (pinfunction "LA18_N_CC_C23") (pintype "bidirectional"))
    )
    (net (code "97") (name "G_D25") (class "Default")
      (node (ref "FRAMEGRABBER") (pin "5") (pinfunction "RXOUT25_5") (pintype "output"))
      (node (ref "U$1") (pin "D24") (pinfunction "LA23_N_D24") (pintype "bidirectional"))
    )
    (net (code "98") (name "G_D26") (class "Default")
      (node (ref "FRAMEGRABBER") (pin "6") (pinfunction "RXOUT26_6") (pintype "output"))
      (node (ref "U$1") (pin "C26") (pinfunction "LA27_P_C26") (pintype "bidirectional"))
    )
    (net (code "99") (name "G_D27") (class "Default")
      (node (ref "FRAMEGRABBER") (pin "7") (pinfunction "RXOUT27_7") (pintype "output"))
      (node (ref "U$1") (pin "C27") (pinfunction "LA27_N_C27") (pintype "bidirectional"))
    )
    (net (code "100") (name "G_SERFC") (class "Default")
      (node (ref "SER_IN") (pin "4") (pinfunction "ROUT_4") (pintype "output"))
      (node (ref "U$1") (pin "G37") (pinfunction "LA33_N_G37") (pintype "bidirectional"))
    )
    (net (code "101") (name "G_SERFC_N") (class "Default")
      (node (ref "CL_IN") (pin "19") (pinfunction "19_19") (pintype "passive"))
      (node (ref "R6") (pin "2") (pinfunction "2_2") (pintype "passive"))
      (node (ref "SER_IN") (pin "9") (pinfunction "RI-_9") (pintype "input"))
    )
    (net (code "102") (name "G_SERFC_P") (class "Default")
      (node (ref "CL_IN") (pin "6") (pinfunction "6_6") (pintype "passive"))
      (node (ref "R6") (pin "1") (pinfunction "1_1") (pintype "passive"))
      (node (ref "SER_IN") (pin "10") (pinfunction "RI+_10") (pintype "input"))
    )
    (net (code "103") (name "G_SERTC") (class "Default")
      (node (ref "SER_IN") (pin "2") (pinfunction "DIN_2") (pintype "input"))
      (node (ref "U$1") (pin "H38") (pinfunction "LA32_N_H38") (pintype "bidirectional"))
    )
    (net (code "104") (name "G_SERTC_N") (class "Default")
      (node (ref "CL_IN") (pin "7") (pinfunction "7_7") (pintype "passive"))
      (node (ref "SER_IN") (pin "11") (pinfunction "DO-_11") (pintype "output"))
    )
    (net (code "105") (name "G_SERTC_P") (class "Default")
      (node (ref "CL_IN") (pin "20") (pinfunction "20_20") (pintype "passive"))
      (node (ref "SER_IN") (pin "12") (pinfunction "DO+_12") (pintype "output"))
    )
    (net (code "106") (name "G_X0_N") (class "Default")
      (node (ref "CL_IN") (pin "25") (pinfunction "25_25") (pintype "passive"))
      (node (ref "FRAMEGRABBER") (pin "9") (pinfunction "RXIN0-_9") (pintype "input"))
      (node (ref "R10") (pin "2") (pinfunction "2_2") (pintype "passive"))
    )
    (net (code "107") (name "G_X0_P") (class "Default")
      (node (ref "CL_IN") (pin "12") (pinfunction "12_12") (pintype "passive"))
      (node (ref "FRAMEGRABBER") (pin "10") (pinfunction "RXIN0+_10") (pintype "input"))
      (node (ref "R10") (pin "1") (pinfunction "1_1") (pintype "passive"))
    )
    (net (code "108") (name "G_X1_N") (class "Default")
      (node (ref "CL_IN") (pin "24") (pinfunction "24_24") (pintype "passive"))
      (node (ref "FRAMEGRABBER") (pin "11") (pinfunction "RXIN1-_11") (pintype "input"))
      (node (ref "R9") (pin "2") (pinfunction "2_2") (pintype "passive"))
    )
    (net (code "109") (name "G_X1_P") (class "Default")
      (node (ref "CL_IN") (pin "11") (pinfunction "11_11") (pintype "passive"))
      (node (ref "FRAMEGRABBER") (pin "12") (pinfunction "RXIN1+_12") (pintype "input"))
      (node (ref "R9") (pin "1") (pinfunction "1_1") (pintype "passive"))
    )
    (net (code "110") (name "G_X2_N") (class "Default")
      (node (ref "CL_IN") (pin "23") (pinfunction "23_23") (pintype "passive"))
      (node (ref "FRAMEGRABBER") (pin "15") (pinfunction "RXIN2-_15") (pintype "input"))
      (node (ref "R8") (pin "2") (pinfunction "2_2") (pintype "passive"))
    )
    (net (code "111") (name "G_X2_P") (class "Default")
      (node (ref "CL_IN") (pin "10") (pinfunction "10_10") (pintype "passive"))
      (node (ref "FRAMEGRABBER") (pin "16") (pinfunction "RXIN2+_16") (pintype "input"))
      (node (ref "R8") (pin "1") (pinfunction "1_1") (pintype "passive"))
    )
    (net (code "112") (name "G_X3_N") (class "Default")
      (node (ref "CL_IN") (pin "21") (pinfunction "21_21") (pintype "passive"))
      (node (ref "FRAMEGRABBER") (pin "19") (pinfunction "RXIN3-_19") (pintype "input"))
      (node (ref "R7") (pin "2") (pinfunction "2_2") (pintype "passive"))
    )
    (net (code "113") (name "G_X3_P") (class "Default")
      (node (ref "CL_IN") (pin "8") (pinfunction "8_8") (pintype "passive"))
      (node (ref "FRAMEGRABBER") (pin "20") (pinfunction "RXIN3+_20") (pintype "input"))
      (node (ref "R7") (pin "1") (pinfunction "1_1") (pintype "passive"))
    )
    (net (code "114") (name "G_XCLK_N") (class "Default")
      (node (ref "CL_IN") (pin "22") (pinfunction "22_22") (pintype "passive"))
      (node (ref "FRAMEGRABBER") (pin "17") (pinfunction "RXCLKIN-_17") (pintype "input"))
      (node (ref "R11") (pin "2") (pinfunction "2_2") (pintype "passive"))
    )
    (net (code "115") (name "G_XCLK_P") (class "Default")
      (node (ref "CL_IN") (pin "9") (pinfunction "9_9") (pintype "passive"))
      (node (ref "FRAMEGRABBER") (pin "18") (pinfunction "RXCLKIN+_18") (pintype "input"))
      (node (ref "R11") (pin "1") (pinfunction "1_1") (pintype "passive"))
    )
    (net (code "116") (name "Net-(CL_IN-Pad1)") (class "Default")
      (node (ref "CL_IN") (pin "1") (pinfunction "1_1") (pintype "passive"))
      (node (ref "CL_IN") (pin "13") (pinfunction "13_13") (pintype "passive"))
      (node (ref "CL_IN") (pin "14") (pinfunction "14_14") (pintype "passive"))
      (node (ref "CL_IN") (pin "26") (pinfunction "26_26") (pintype "passive"))
    )
    (net (code "117") (name "Net-(CL_OUT-Pad1)") (class "Default")
      (node (ref "CL_OUT") (pin "1") (pinfunction "1_1") (pintype "passive"))
      (node (ref "CL_OUT") (pin "13") (pinfunction "13_13") (pintype "passive"))
      (node (ref "CL_OUT") (pin "14") (pinfunction "14_14") (pintype "passive"))
      (node (ref "CL_OUT") (pin "26") (pinfunction "26_26") (pintype "passive"))
    )
    (net (code "118") (name "VCC") (class "Default")
      (node (ref "C1") (pin "1") (pinfunction "1_1") (pintype "passive"))
      (node (ref "C2") (pin "1") (pinfunction "1_1") (pintype "passive"))
      (node (ref "C3") (pin "1") (pinfunction "1_1") (pintype "passive"))
      (node (ref "C4") (pin "1") (pinfunction "1_1") (pintype "passive"))
      (node (ref "C5") (pin "1") (pinfunction "1_1") (pintype "passive"))
      (node (ref "C6") (pin "1") (pinfunction "1_1") (pintype "passive"))
      (node (ref "C7") (pin "1") (pinfunction "1_1") (pintype "passive"))
      (node (ref "CC_IN") (pin "1") (pinfunction "EN_1") (pintype "input"))
      (node (ref "CC_IN") (pin "4") (pinfunction "VCC_4") (pintype "power_in"))
      (node (ref "CC_OUT") (pin "13") (pinfunction "VCC_13") (pintype "power_in"))
      (node (ref "CC_OUT") (pin "16") (pinfunction "EN_16") (pintype "input"))
      (node (ref "FRAMEGRABBER") (pin "13") (pinfunction "LVDSVCC_13") (pintype "power_in"))
      (node (ref "FRAMEGRABBER") (pin "23") (pinfunction "PLLVCC_23") (pintype "power_in"))
      (node (ref "FRAMEGRABBER") (pin "25") (pinfunction "~{PWRDWN}_25") (pintype "passive"))
      (node (ref "FRAMEGRABBER") (pin "31") (pinfunction "VCC_2_31") (pintype "power_in"))
      (node (ref "FRAMEGRABBER") (pin "40") (pinfunction "VCC_3_40") (pintype "power_in"))
      (node (ref "FRAMEGRABBER") (pin "48") (pinfunction "VCC_48") (pintype "power_in"))
      (node (ref "FRAMEGRABBER") (pin "56") (pinfunction "VCC_4_56") (pintype "power_in"))
      (node (ref "FRAMEPUSHER") (pin "1") (pinfunction "VCC_4_1") (pintype "power_in"))
      (node (ref "FRAMEPUSHER") (pin "17") (pinfunction "VCC_2_17") (pintype "power_in"))
      (node (ref "FRAMEPUSHER") (pin "26") (pinfunction "VCC_3_26") (pintype "power_in"))
      (node (ref "FRAMEPUSHER") (pin "32") (pinfunction "~{PWRDWN}_32") (pintype "input"))
      (node (ref "FRAMEPUSHER") (pin "34") (pinfunction "PLLVCC_34") (pintype "power_in"))
      (node (ref "FRAMEPUSHER") (pin "44") (pinfunction "LVDSVCC_44") (pintype "power_in"))
      (node (ref "FRAMEPUSHER") (pin "9") (pinfunction "VCC_9") (pintype "power_in"))
      (node (ref "SER_IN") (pin "1") (pinfunction "DE_1") (pintype "input"))
      (node (ref "SER_IN") (pin "14") (pinfunction "VCC_14") (pintype "power_in"))
      (node (ref "SER_OUT") (pin "1") (pinfunction "DE_1") (pintype "input"))
      (node (ref "SER_OUT") (pin "14") (pinfunction "VCC_14") (pintype "power_in"))
      (node (ref "U$1") (pin "C39") (pinfunction "3V3_C39") (pintype "bidirectional"))
      (node (ref "U$1") (pin "D36") (pinfunction "3V3_2_D36") (pintype "bidirectional"))
      (node (ref "U$1") (pin "D38") (pinfunction "3V3_3_D38") (pintype "bidirectional"))
      (node (ref "U$1") (pin "D40") (pinfunction "3V3_4_D40") (pintype "bidirectional"))
    )
    (net (code "119") (name "unconnected-(SER_IN-NC-Pad6)") (class "Default")
      (node (ref "SER_IN") (pin "6") (pinfunction "NC_6") (pintype "no_connect"))
    )
    (net (code "120") (name "unconnected-(SER_IN-NC_2-Pad3)") (class "Default")
      (node (ref "SER_IN") (pin "3") (pinfunction "NC_2_3") (pintype "no_connect"))
    )
    (net (code "121") (name "unconnected-(SER_IN-NC_3-Pad5)") (class "Default")
      (node (ref "SER_IN") (pin "5") (pinfunction "NC_3_5") (pintype "no_connect"))
    )
    (net (code "122") (name "unconnected-(SER_IN-NC_4-Pad13)") (class "Default")
      (node (ref "SER_IN") (pin "13") (pinfunction "NC_4_13") (pintype "no_connect"))
    )
    (net (code "123") (name "unconnected-(SER_OUT-NC-Pad6)") (class "Default")
      (node (ref "SER_OUT") (pin "6") (pinfunction "NC_6") (pintype "no_connect"))
    )
    (net (code "124") (name "unconnected-(SER_OUT-NC_2-Pad3)") (class "Default")
      (node (ref "SER_OUT") (pin "3") (pinfunction "NC_2_3") (pintype "no_connect"))
    )
    (net (code "125") (name "unconnected-(SER_OUT-NC_3-Pad5)") (class "Default")
      (node (ref "SER_OUT") (pin "5") (pinfunction "NC_3_5") (pintype "no_connect"))
    )
    (net (code "126") (name "unconnected-(SER_OUT-NC_4-Pad13)") (class "Default")
      (node (ref "SER_OUT") (pin "13") (pinfunction "NC_4_13") (pintype "no_connect"))
    )
    (net (code "127") (name "unconnected-(U$1-3V3AUX-PadD32)") (class "Default")
      (node (ref "U$1") (pin "D32") (pinfunction "3V3AUX_D32") (pintype "bidirectional"))
    )
    (net (code "128") (name "unconnected-(U$1-12V0-PadC35)") (class "Default")
      (node (ref "U$1") (pin "C35") (pinfunction "12V0_C35") (pintype "bidirectional"))
    )
    (net (code "129") (name "unconnected-(U$1-12V0_2-PadC37)") (class "Default")
      (node (ref "U$1") (pin "C37") (pinfunction "12V0_2_C37") (pintype "bidirectional"))
    )
    (net (code "130") (name "unconnected-(U$1-CLK1-M2C_N-PadG3)") (class "Default")
      (node (ref "U$1") (pin "G3") (pinfunction "CLK1-M2C_N_G3") (pintype "bidirectional"))
    )
    (net (code "131") (name "unconnected-(U$1-CLK1-M2C_P-PadG2)") (class "Default")
      (node (ref "U$1") (pin "G2") (pinfunction "CLK1-M2C_P_G2") (pintype "bidirectional"))
    )
    (net (code "132") (name "unconnected-(U$1-DP0-C2M_N-PadC3)") (class "Default")
      (node (ref "U$1") (pin "C3") (pinfunction "DP0-C2M_N_C3") (pintype "bidirectional"))
    )
    (net (code "133") (name "unconnected-(U$1-DP0-C2M_P-PadC2)") (class "Default")
      (node (ref "U$1") (pin "C2") (pinfunction "DP0-C2M_P_C2") (pintype "bidirectional"))
    )
    (net (code "134") (name "unconnected-(U$1-DP0-M2C_N-PadC7)") (class "Default")
      (node (ref "U$1") (pin "C7") (pinfunction "DP0-M2C_N_C7") (pintype "bidirectional"))
    )
    (net (code "135") (name "unconnected-(U$1-DP0-M2C_P-PadC6)") (class "Default")
      (node (ref "U$1") (pin "C6") (pinfunction "DP0-M2C_P_C6") (pintype "bidirectional"))
    )
    (net (code "136") (name "unconnected-(U$1-GBTCLK0-M2C_N-PadD5)") (class "Default")
      (node (ref "U$1") (pin "D5") (pinfunction "GBTCLK0-M2C_N_D5") (pintype "bidirectional"))
    )
    (net (code "137") (name "unconnected-(U$1-GBTCLK0-M2C_P-PadD4)") (class "Default")
      (node (ref "U$1") (pin "D4") (pinfunction "GBTCLK0-M2C_P_D4") (pintype "bidirectional"))
    )
    (net (code "138") (name "unconnected-(U$1-PG_C2M-PadD1)") (class "Default")
      (node (ref "U$1") (pin "D1") (pinfunction "PG_C2M_D1") (pintype "bidirectional"))
    )
    (net (code "139") (name "unconnected-(U$1-PRSNT-M2C_L-PadH2)") (class "Default")
      (node (ref "U$1") (pin "H2") (pinfunction "PRSNT-M2C_L_H2") (pintype "bidirectional"))
    )
    (net (code "140") (name "unconnected-(U$1-SCL-PadC30)") (class "Default")
      (node (ref "U$1") (pin "C30") (pinfunction "SCL_C30") (pintype "bidirectional"))
    )
    (net (code "141") (name "unconnected-(U$1-SDA-PadC31)") (class "Default")
      (node (ref "U$1") (pin "C31") (pinfunction "SDA_C31") (pintype "bidirectional"))
    )
    (net (code "142") (name "unconnected-(U$1-TCK-PadD29)") (class "Default")
      (node (ref "U$1") (pin "D29") (pinfunction "TCK_D29") (pintype "bidirectional"))
    )
    (net (code "143") (name "unconnected-(U$1-TDI-PadD30)") (class "Default")
      (node (ref "U$1") (pin "D30") (pinfunction "TDI_D30") (pintype "bidirectional"))
    )
    (net (code "144") (name "unconnected-(U$1-TDO-PadD31)") (class "Default")
      (node (ref "U$1") (pin "D31") (pinfunction "TDO_D31") (pintype "bidirectional"))
    )
    (net (code "145") (name "unconnected-(U$1-TMS-PadD33)") (class "Default")
      (node (ref "U$1") (pin "D33") (pinfunction "TMS_D33") (pintype "bidirectional"))
    )
    (net (code "146") (name "unconnected-(U$1-TRST_L-PadD34)") (class "Default")
      (node (ref "U$1") (pin "D34") (pinfunction "TRST_L_D34") (pintype "bidirectional"))
    )
    (net (code "147") (name "unconnected-(U$1-VADJ_3-PadG39)") (class "Default")
      (node (ref "U$1") (pin "G39") (pinfunction "VADJ_3_G39") (pintype "bidirectional"))
    )
    (net (code "148") (name "unconnected-(U$1-VADJ_4-PadH40)") (class "Default")
      (node (ref "U$1") (pin "H40") (pinfunction "VADJ_4_H40") (pintype "bidirectional"))
    )
    (net (code "149") (name "unconnected-(U$1-VREF-A-M2C-PadH1)") (class "Default")
      (node (ref "U$1") (pin "H1") (pinfunction "VREF-A-M2C_H1") (pintype "bidirectional"))
    )
  )
)
